# BEE_BOARD_DECAWAVE.net
KiCad netlist of a schematic drawn in Altium Designer
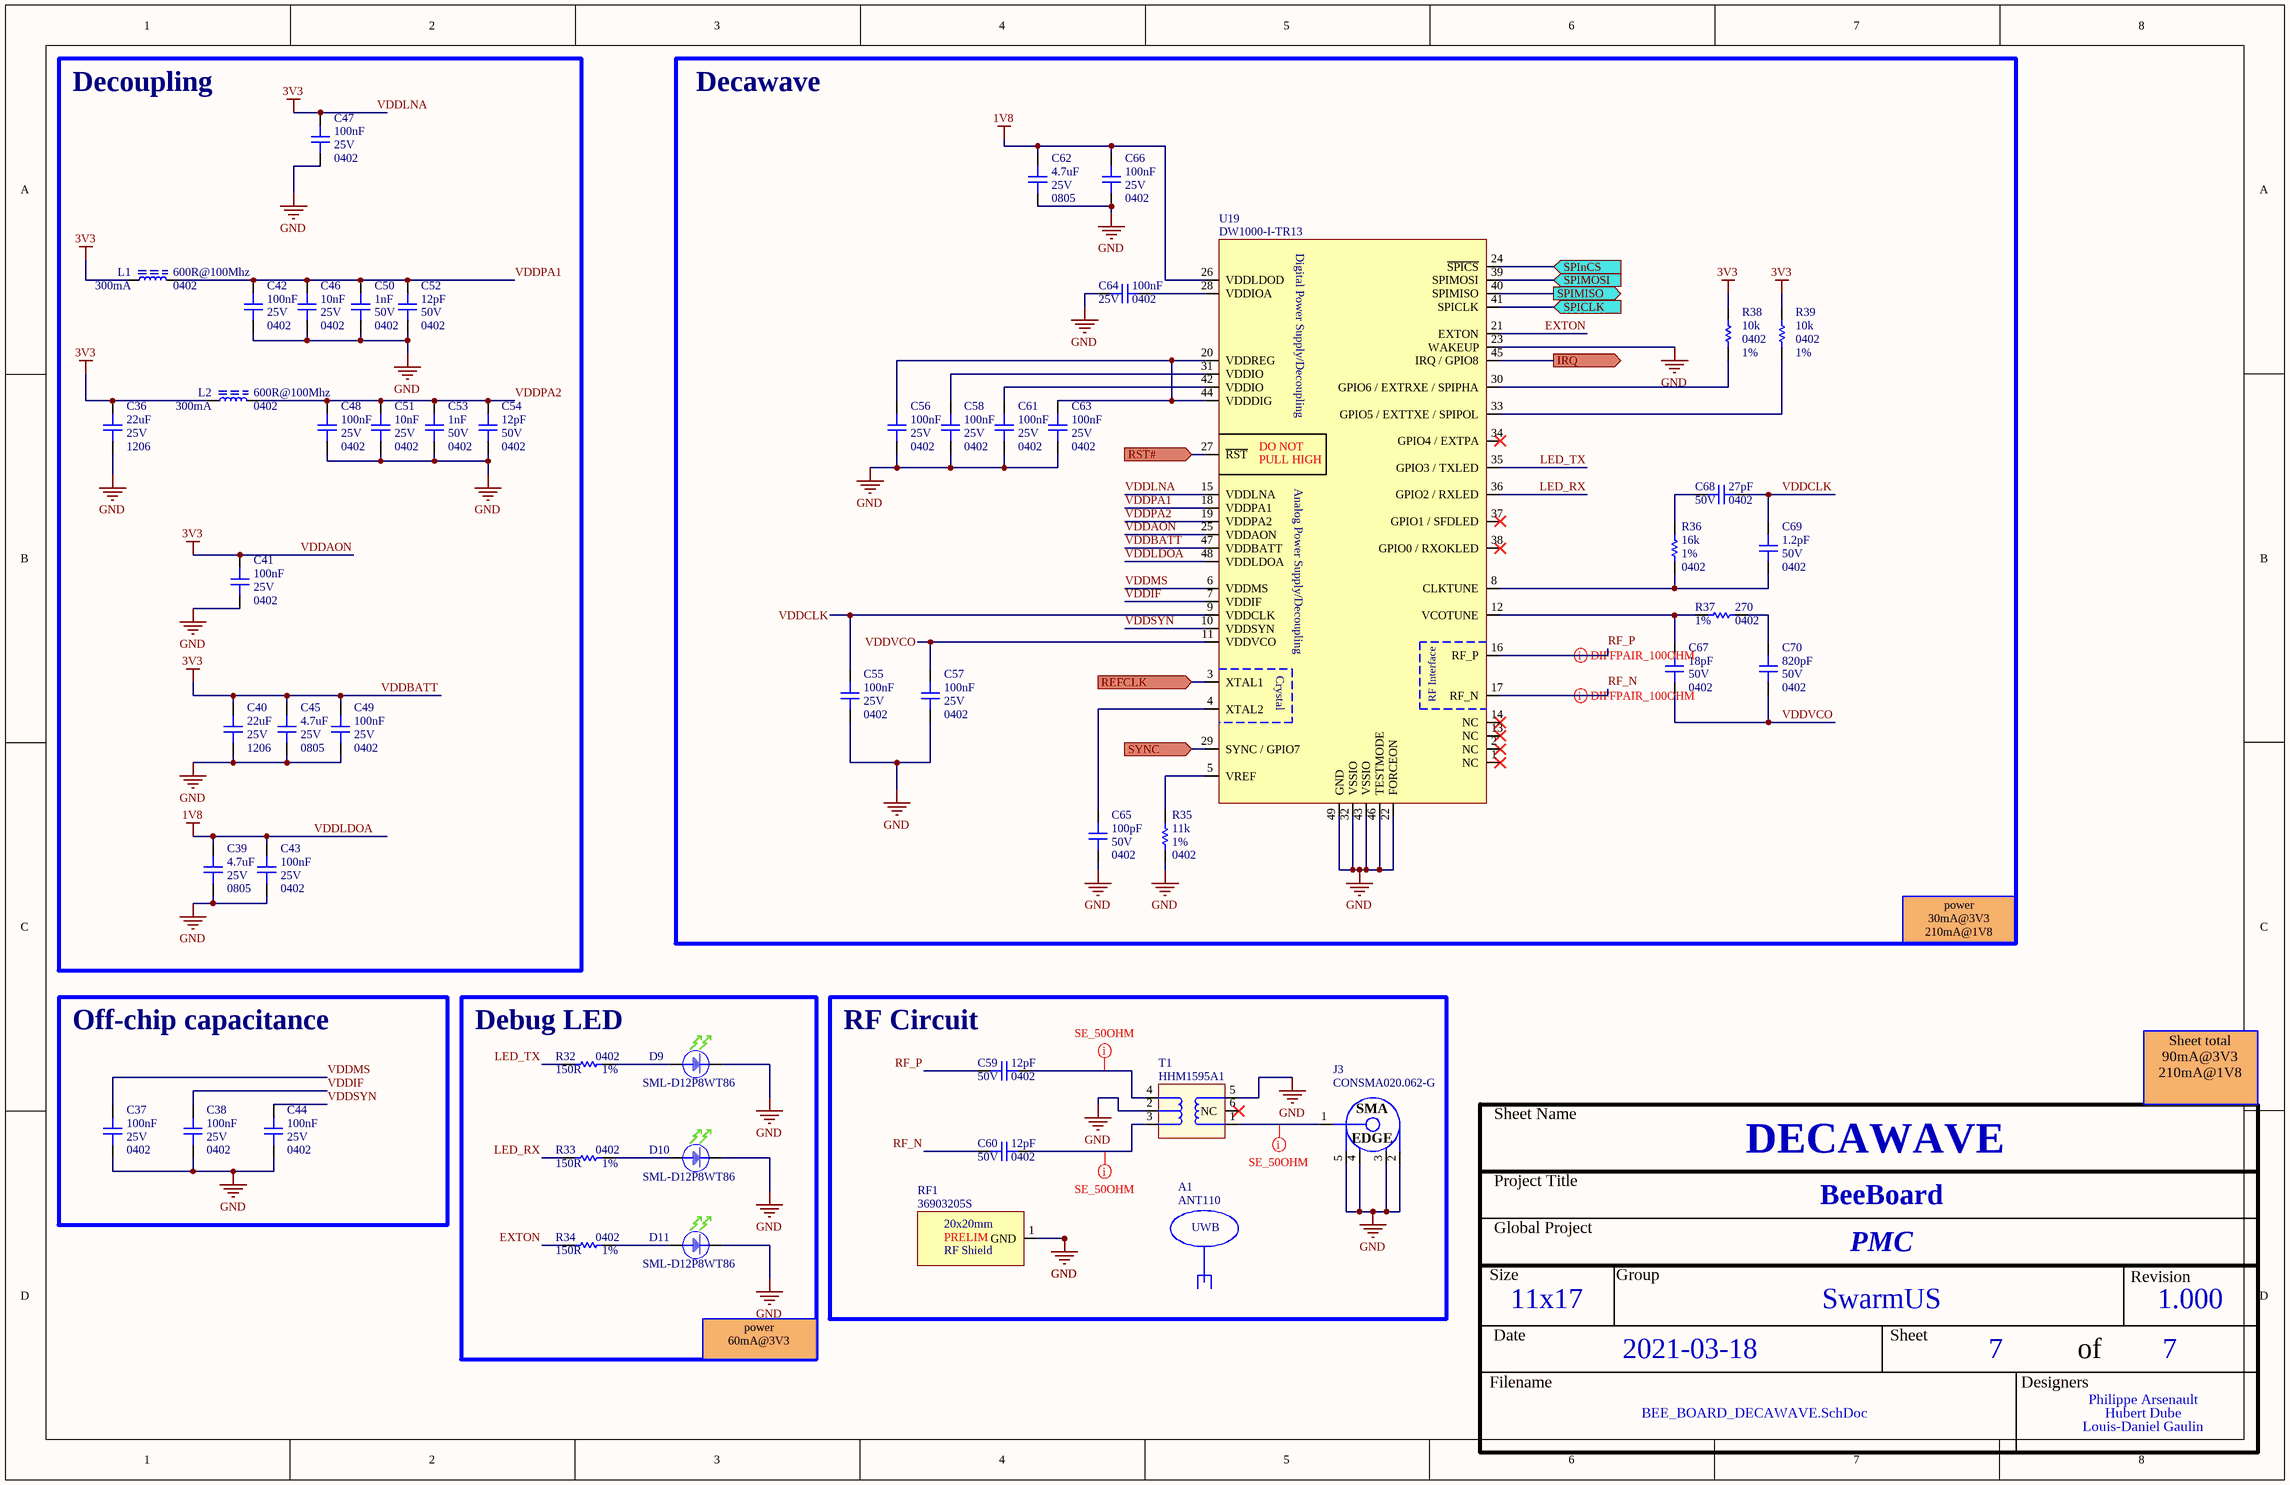
[diagram p0: BEE_BOARD_DECAWAVE.SchDoc]

(export (version "E")
  (design (tool "Eeschema 10.0.6"))
  (components
    (comp (ref "A1")
      (value "ANT110")
      (description "ANT - UWB antenna 3.2 to 7GHz")
      (fields
        (field (name "CREATEDBY/DATE") "Philippe Arsenault/2021-04-11")
        (field (name "VERIFIEDBY") "Louis-Daniel Gaulin / 14-04-2021")
      )
      (libsource (lib "SWARMUS_LIB") (part "ANT_ANT110"))
    )
    (comp (ref "C36")
      (value "22uF")
      (footprint "grams_master_lib_pcb:CAP_CER_1206")
      (description "CAP - CER 22uF 10% 25V X5R - 1206")
      (fields
        (field (name "TOLERANCE") "10%")
        (field (name "PACKAGE") "1206")
        (field (name "VOLTAGE RATING") "25V")
        (field (name "Comment") "CL31A226KAHNNNE")
        (field (name "CREATEDBY/DATE") "Philippe Arsenault/21 Janvier 2020")
        (field (name "VERIFIEDBY") "C.Paulin - 28/01/2020")
      )
      (libsource (lib "GRAMS_MASTER_LIB_SCH") (part "CAP_CER_CL31A226KAHNNNE"))
    )
    (comp (ref "C37")
      (value "100nF")
      (footprint "GRAMS_MASTER_LIB_PCB:CAP_CER_0402")
      (description "CAP - CER 0.1µF 10% 25V X7R - 0402")
      (fields
        (field (name "TOLERANCE") "10%")
        (field (name "PACKAGE") "0402")
        (field (name "VOLTAGE RATING") "25V")
        (field (name "Comment") "CGA2B3X7R1E104K050BB")
        (field (name "CREATEDBY/DATE") "Nicolas Roy 2018-11-07")
        (field (name "VERIFIEDBY") "Nicolas V. (2019-01-22)")
      )
      (libsource (lib "GRAMS_MASTER_LIB_SCH") (part "CAP_CER_CGA2B3X7R1E104K050BB"))
    )
    (comp (ref "C38")
      (value "100nF")
      (footprint "GRAMS_MASTER_LIB_PCB:CAP_CER_0402")
      (description "CAP - CER 0.1µF 10% 25V X7R - 0402")
      (fields
        (field (name "TOLERANCE") "10%")
        (field (name "PACKAGE") "0402")
        (field (name "VOLTAGE RATING") "25V")
        (field (name "Comment") "CGA2B3X7R1E104K050BB")
        (field (name "CREATEDBY/DATE") "Nicolas Roy 2018-11-07")
        (field (name "VERIFIEDBY") "Nicolas V. (2019-01-22)")
      )
      (libsource (lib "GRAMS_MASTER_LIB_SCH") (part "CAP_CER_CGA2B3X7R1E104K050BB"))
    )
    (comp (ref "C39")
      (value "4.7uF")
      (footprint "GRAMS_MASTER_LIB_PCB:CAP_CER_0805")
      (description "CAP - CER 4.7UF 10% 25V X7R - 0805")
      (fields
        (field (name "TOLERANCE") "10%")
        (field (name "PACKAGE") "0805")
        (field (name "VOLTAGE RATING") "25V")
        (field (name "Comment") "C2012X7R1E475K125AE")
        (field (name "CREATEDBY/DATE") "Keven Deslandes - 2018/11/09")
        (field (name "VERIFIEDBY") "Nicolas Roy - 2018/12/11")
      )
      (libsource (lib "GRAMS_MASTER_LIB_SCH") (part "CAP_CER_C2012X7R1E475K125AE"))
    )
    (comp (ref "C40")
      (value "22uF")
      (footprint "grams_master_lib_pcb:CAP_CER_1206")
      (description "CAP - CER 22uF 10% 25V X5R - 1206")
      (fields
        (field (name "TOLERANCE") "10%")
        (field (name "PACKAGE") "1206")
        (field (name "VOLTAGE RATING") "25V")
        (field (name "Comment") "CL31A226KAHNNNE")
        (field (name "CREATEDBY/DATE") "Philippe Arsenault/21 Janvier 2020")
        (field (name "VERIFIEDBY") "C.Paulin - 28/01/2020")
      )
      (libsource (lib "GRAMS_MASTER_LIB_SCH") (part "CAP_CER_CL31A226KAHNNNE"))
    )
    (comp (ref "C41")
      (value "100nF")
      (footprint "GRAMS_MASTER_LIB_PCB:CAP_CER_0402")
      (description "CAP - CER 0.1µF 10% 25V X7R - 0402")
      (fields
        (field (name "TOLERANCE") "10%")
        (field (name "PACKAGE") "0402")
        (field (name "VOLTAGE RATING") "25V")
        (field (name "Comment") "CGA2B3X7R1E104K050BB")
        (field (name "CREATEDBY/DATE") "Nicolas Roy 2018-11-07")
        (field (name "VERIFIEDBY") "Nicolas V. (2019-01-22)")
      )
      (libsource (lib "GRAMS_MASTER_LIB_SCH") (part "CAP_CER_CGA2B3X7R1E104K050BB"))
    )
    (comp (ref "C42")
      (value "100nF")
      (footprint "GRAMS_MASTER_LIB_PCB:CAP_CER_0402")
      (description "CAP - CER 0.1µF 10% 25V X7R - 0402")
      (fields
        (field (name "TOLERANCE") "10%")
        (field (name "PACKAGE") "0402")
        (field (name "VOLTAGE RATING") "25V")
        (field (name "Comment") "CGA2B3X7R1E104K050BB")
        (field (name "CREATEDBY/DATE") "Nicolas Roy 2018-11-07")
        (field (name "VERIFIEDBY") "Nicolas V. (2019-01-22)")
      )
      (libsource (lib "GRAMS_MASTER_LIB_SCH") (part "CAP_CER_CGA2B3X7R1E104K050BB"))
    )
    (comp (ref "C43")
      (value "100nF")
      (footprint "GRAMS_MASTER_LIB_PCB:CAP_CER_0402")
      (description "CAP - CER 0.1µF 10% 25V X7R - 0402")
      (fields
        (field (name "TOLERANCE") "10%")
        (field (name "PACKAGE") "0402")
        (field (name "VOLTAGE RATING") "25V")
        (field (name "Comment") "CGA2B3X7R1E104K050BB")
        (field (name "CREATEDBY/DATE") "Nicolas Roy 2018-11-07")
        (field (name "VERIFIEDBY") "Nicolas V. (2019-01-22)")
      )
      (libsource (lib "GRAMS_MASTER_LIB_SCH") (part "CAP_CER_CGA2B3X7R1E104K050BB"))
    )
    (comp (ref "C44")
      (value "100nF")
      (footprint "GRAMS_MASTER_LIB_PCB:CAP_CER_0402")
      (description "CAP - CER 0.1µF 10% 25V X7R - 0402")
      (fields
        (field (name "TOLERANCE") "10%")
        (field (name "PACKAGE") "0402")
        (field (name "VOLTAGE RATING") "25V")
        (field (name "Comment") "CGA2B3X7R1E104K050BB")
        (field (name "CREATEDBY/DATE") "Nicolas Roy 2018-11-07")
        (field (name "VERIFIEDBY") "Nicolas V. (2019-01-22)")
      )
      (libsource (lib "GRAMS_MASTER_LIB_SCH") (part "CAP_CER_CGA2B3X7R1E104K050BB"))
    )
    (comp (ref "C45")
      (value "4.7uF")
      (footprint "GRAMS_MASTER_LIB_PCB:CAP_CER_0805")
      (description "CAP - CER 4.7UF 10% 25V X7R - 0805")
      (fields
        (field (name "TOLERANCE") "10%")
        (field (name "PACKAGE") "0805")
        (field (name "VOLTAGE RATING") "25V")
        (field (name "Comment") "C2012X7R1E475K125AE")
        (field (name "CREATEDBY/DATE") "Keven Deslandes - 2018/11/09")
        (field (name "VERIFIEDBY") "Nicolas Roy - 2018/12/11")
      )
      (libsource (lib "GRAMS_MASTER_LIB_SCH") (part "CAP_CER_C2012X7R1E475K125AE"))
    )
    (comp (ref "C46")
      (value "10nF")
      (footprint "GRAMS_MASTER_LIB_PCB:CAP_CER_0402")
      (description "CAP - CER 10nF 10% 25V X7R - 0402")
      (fields
        (field (name "TOLERANCE") "10%")
        (field (name "PACKAGE") "0402")
        (field (name "VOLTAGE RATING") "25V")
        (field (name "Comment") "CL05B103KA5NNNC")
        (field (name "CREATEDBY/DATE") "Romain Espagnet 2018-07-16")
        (field (name "VERIFIEDBY") "Jonathan Bouchard 2018-07-30")
      )
      (libsource (lib "GRAMS_MASTER_LIB_SCH") (part "CAP_CER_CL05B103KA5NNNC"))
    )
    (comp (ref "C47")
      (value "100nF")
      (footprint "GRAMS_MASTER_LIB_PCB:CAP_CER_0402")
      (description "CAP - CER 0.1µF 10% 25V X7R - 0402")
      (fields
        (field (name "TOLERANCE") "10%")
        (field (name "PACKAGE") "0402")
        (field (name "VOLTAGE RATING") "25V")
        (field (name "Comment") "CGA2B3X7R1E104K050BB")
        (field (name "CREATEDBY/DATE") "Nicolas Roy 2018-11-07")
        (field (name "VERIFIEDBY") "Nicolas V. (2019-01-22)")
      )
      (libsource (lib "GRAMS_MASTER_LIB_SCH") (part "CAP_CER_CGA2B3X7R1E104K050BB"))
    )
    (comp (ref "C48")
      (value "100nF")
      (footprint "GRAMS_MASTER_LIB_PCB:CAP_CER_0402")
      (description "CAP - CER 0.1µF 10% 25V X7R - 0402")
      (fields
        (field (name "TOLERANCE") "10%")
        (field (name "PACKAGE") "0402")
        (field (name "VOLTAGE RATING") "25V")
        (field (name "Comment") "CGA2B3X7R1E104K050BB")
        (field (name "CREATEDBY/DATE") "Nicolas Roy 2018-11-07")
        (field (name "VERIFIEDBY") "Nicolas V. (2019-01-22)")
      )
      (libsource (lib "GRAMS_MASTER_LIB_SCH") (part "CAP_CER_CGA2B3X7R1E104K050BB"))
    )
    (comp (ref "C49")
      (value "100nF")
      (footprint "GRAMS_MASTER_LIB_PCB:CAP_CER_0402")
      (description "CAP - CER 0.1µF 10% 25V X7R - 0402")
      (fields
        (field (name "TOLERANCE") "10%")
        (field (name "PACKAGE") "0402")
        (field (name "VOLTAGE RATING") "25V")
        (field (name "Comment") "CGA2B3X7R1E104K050BB")
        (field (name "CREATEDBY/DATE") "Nicolas Roy 2018-11-07")
        (field (name "VERIFIEDBY") "Nicolas V. (2019-01-22)")
      )
      (libsource (lib "GRAMS_MASTER_LIB_SCH") (part "CAP_CER_CGA2B3X7R1E104K050BB"))
    )
    (comp (ref "C50")
      (value "1nF")
      (footprint "CAP_CER_0402")
      (description "CAP - CER 1nF 10% 50V X7R - 0402")
      (fields
        (field (name "TOLERANCE") "10%")
        (field (name "PACKAGE") "0402")
        (field (name "VOLTAGE RATING") "50V")
        (field (name "Comment") "CC0402KRX7R9BB102")
        (field (name "CREATEDBY/DATE") "Jonathan Bouchard 2019-04-06")
        (field (name "VERIFIEDBY") "Nicolas V. (2019-04-30)")
      )
      (libsource (lib "GRAMS_MASTER_LIB_SCH") (part "CAP_CER_CC0402KRX7R9BB102"))
    )
    (comp (ref "C51")
      (value "10nF")
      (footprint "GRAMS_MASTER_LIB_PCB:CAP_CER_0402")
      (description "CAP - CER 10nF 10% 25V X7R - 0402")
      (fields
        (field (name "TOLERANCE") "10%")
        (field (name "PACKAGE") "0402")
        (field (name "VOLTAGE RATING") "25V")
        (field (name "Comment") "CL05B103KA5NNNC")
        (field (name "CREATEDBY/DATE") "Romain Espagnet 2018-07-16")
        (field (name "VERIFIEDBY") "Jonathan Bouchard 2018-07-30")
      )
      (libsource (lib "GRAMS_MASTER_LIB_SCH") (part "CAP_CER_CL05B103KA5NNNC"))
    )
    (comp (ref "C52")
      (value "12pF")
      (footprint "SWARMUS_LIB:CAP_CER_0402")
      (description "CAP - CER 12pF 50V ±5% C0G, NP0 - 0402")
      (fields
        (field (name "TOLERANCE") "±5%")
        (field (name "PACKAGE") "0402")
        (field (name "VOLTAGE RATING") "50V")
        (field (name "Comment") "CC0402JRNPO9BN120")
        (field (name "CREATEDBY/DATE") "Philippe Arsenault/ 2020-07-24")
        (field (name "VERIFIEDBY") "Louis-Daniel Gaulin / 2020-07-29")
      )
      (libsource (lib "SWARMUS_LIB") (part "CAP_CER_CC0402JRNPO9BN120"))
    )
    (comp (ref "C53")
      (value "1nF")
      (footprint "CAP_CER_0402")
      (description "CAP - CER 1nF 10% 50V X7R - 0402")
      (fields
        (field (name "TOLERANCE") "10%")
        (field (name "PACKAGE") "0402")
        (field (name "VOLTAGE RATING") "50V")
        (field (name "Comment") "CC0402KRX7R9BB102")
        (field (name "CREATEDBY/DATE") "Jonathan Bouchard 2019-04-06")
        (field (name "VERIFIEDBY") "Nicolas V. (2019-04-30)")
      )
      (libsource (lib "GRAMS_MASTER_LIB_SCH") (part "CAP_CER_CC0402KRX7R9BB102"))
    )
    (comp (ref "C54")
      (value "12pF")
      (footprint "SWARMUS_LIB:CAP_CER_0402")
      (description "CAP - CER 12pF 50V ±5% C0G, NP0 - 0402")
      (fields
        (field (name "TOLERANCE") "±5%")
        (field (name "PACKAGE") "0402")
        (field (name "VOLTAGE RATING") "50V")
        (field (name "Comment") "CC0402JRNPO9BN120")
        (field (name "CREATEDBY/DATE") "Philippe Arsenault/ 2020-07-24")
        (field (name "VERIFIEDBY") "Louis-Daniel Gaulin / 2020-07-29")
      )
      (libsource (lib "SWARMUS_LIB") (part "CAP_CER_CC0402JRNPO9BN120"))
    )
    (comp (ref "C55")
      (value "100nF")
      (footprint "GRAMS_MASTER_LIB_PCB:CAP_CER_0402")
      (description "CAP - CER 0.1µF 10% 25V X7R - 0402")
      (fields
        (field (name "TOLERANCE") "10%")
        (field (name "PACKAGE") "0402")
        (field (name "VOLTAGE RATING") "25V")
        (field (name "Comment") "CGA2B3X7R1E104K050BB")
        (field (name "CREATEDBY/DATE") "Nicolas Roy 2018-11-07")
        (field (name "VERIFIEDBY") "Nicolas V. (2019-01-22)")
      )
      (libsource (lib "GRAMS_MASTER_LIB_SCH") (part "CAP_CER_CGA2B3X7R1E104K050BB"))
    )
    (comp (ref "C56")
      (value "100nF")
      (footprint "GRAMS_MASTER_LIB_PCB:CAP_CER_0402")
      (description "CAP - CER 0.1µF 10% 25V X7R - 0402")
      (fields
        (field (name "TOLERANCE") "10%")
        (field (name "PACKAGE") "0402")
        (field (name "VOLTAGE RATING") "25V")
        (field (name "Comment") "CGA2B3X7R1E104K050BB")
        (field (name "CREATEDBY/DATE") "Nicolas Roy 2018-11-07")
        (field (name "VERIFIEDBY") "Nicolas V. (2019-01-22)")
      )
      (libsource (lib "GRAMS_MASTER_LIB_SCH") (part "CAP_CER_CGA2B3X7R1E104K050BB"))
    )
    (comp (ref "C57")
      (value "100nF")
      (footprint "GRAMS_MASTER_LIB_PCB:CAP_CER_0402")
      (description "CAP - CER 0.1µF 10% 25V X7R - 0402")
      (fields
        (field (name "TOLERANCE") "10%")
        (field (name "PACKAGE") "0402")
        (field (name "VOLTAGE RATING") "25V")
        (field (name "Comment") "CGA2B3X7R1E104K050BB")
        (field (name "CREATEDBY/DATE") "Nicolas Roy 2018-11-07")
        (field (name "VERIFIEDBY") "Nicolas V. (2019-01-22)")
      )
      (libsource (lib "GRAMS_MASTER_LIB_SCH") (part "CAP_CER_CGA2B3X7R1E104K050BB"))
    )
    (comp (ref "C58")
      (value "100nF")
      (footprint "GRAMS_MASTER_LIB_PCB:CAP_CER_0402")
      (description "CAP - CER 0.1µF 10% 25V X7R - 0402")
      (fields
        (field (name "TOLERANCE") "10%")
        (field (name "PACKAGE") "0402")
        (field (name "VOLTAGE RATING") "25V")
        (field (name "Comment") "CGA2B3X7R1E104K050BB")
        (field (name "CREATEDBY/DATE") "Nicolas Roy 2018-11-07")
        (field (name "VERIFIEDBY") "Nicolas V. (2019-01-22)")
      )
      (libsource (lib "GRAMS_MASTER_LIB_SCH") (part "CAP_CER_CGA2B3X7R1E104K050BB"))
    )
    (comp (ref "C59")
      (value "12pF")
      (footprint "SWARMUS_LIB:CAP_CER_0402")
      (description "CAP - CER 12pF 50V ±5% C0G, NP0 - 0402")
      (fields
        (field (name "TOLERANCE") "±5%")
        (field (name "PACKAGE") "0402")
        (field (name "VOLTAGE RATING") "50V")
        (field (name "Comment") "CC0402JRNPO9BN120")
        (field (name "CREATEDBY/DATE") "Philippe Arsenault/ 2020-07-24")
        (field (name "VERIFIEDBY") "Louis-Daniel Gaulin / 2020-07-29")
      )
      (libsource (lib "SWARMUS_LIB") (part "CAP_CER_CC0402JRNPO9BN120"))
    )
    (comp (ref "C60")
      (value "12pF")
      (footprint "SWARMUS_LIB:CAP_CER_0402")
      (description "CAP - CER 12pF 50V ±5% C0G, NP0 - 0402")
      (fields
        (field (name "TOLERANCE") "±5%")
        (field (name "PACKAGE") "0402")
        (field (name "VOLTAGE RATING") "50V")
        (field (name "Comment") "CC0402JRNPO9BN120")
        (field (name "CREATEDBY/DATE") "Philippe Arsenault/ 2020-07-24")
        (field (name "VERIFIEDBY") "Louis-Daniel Gaulin / 2020-07-29")
      )
      (libsource (lib "SWARMUS_LIB") (part "CAP_CER_CC0402JRNPO9BN120"))
    )
    (comp (ref "C61")
      (value "100nF")
      (footprint "GRAMS_MASTER_LIB_PCB:CAP_CER_0402")
      (description "CAP - CER 0.1µF 10% 25V X7R - 0402")
      (fields
        (field (name "TOLERANCE") "10%")
        (field (name "PACKAGE") "0402")
        (field (name "VOLTAGE RATING") "25V")
        (field (name "Comment") "CGA2B3X7R1E104K050BB")
        (field (name "CREATEDBY/DATE") "Nicolas Roy 2018-11-07")
        (field (name "VERIFIEDBY") "Nicolas V. (2019-01-22)")
      )
      (libsource (lib "GRAMS_MASTER_LIB_SCH") (part "CAP_CER_CGA2B3X7R1E104K050BB"))
    )
    (comp (ref "C62")
      (value "4.7uF")
      (footprint "GRAMS_MASTER_LIB_PCB:CAP_CER_0805")
      (description "CAP - CER 4.7UF 10% 25V X7R - 0805")
      (fields
        (field (name "TOLERANCE") "10%")
        (field (name "PACKAGE") "0805")
        (field (name "VOLTAGE RATING") "25V")
        (field (name "Comment") "C2012X7R1E475K125AE")
        (field (name "CREATEDBY/DATE") "Keven Deslandes - 2018/11/09")
        (field (name "VERIFIEDBY") "Nicolas Roy - 2018/12/11")
      )
      (libsource (lib "GRAMS_MASTER_LIB_SCH") (part "CAP_CER_C2012X7R1E475K125AE"))
    )
    (comp (ref "C63")
      (value "100nF")
      (footprint "GRAMS_MASTER_LIB_PCB:CAP_CER_0402")
      (description "CAP - CER 0.1µF 10% 25V X7R - 0402")
      (fields
        (field (name "TOLERANCE") "10%")
        (field (name "PACKAGE") "0402")
        (field (name "VOLTAGE RATING") "25V")
        (field (name "Comment") "CGA2B3X7R1E104K050BB")
        (field (name "CREATEDBY/DATE") "Nicolas Roy 2018-11-07")
        (field (name "VERIFIEDBY") "Nicolas V. (2019-01-22)")
      )
      (libsource (lib "GRAMS_MASTER_LIB_SCH") (part "CAP_CER_CGA2B3X7R1E104K050BB"))
    )
    (comp (ref "C64")
      (value "100nF")
      (footprint "GRAMS_MASTER_LIB_PCB:CAP_CER_0402")
      (description "CAP - CER 0.1µF 10% 25V X7R - 0402")
      (fields
        (field (name "TOLERANCE") "10%")
        (field (name "PACKAGE") "0402")
        (field (name "VOLTAGE RATING") "25V")
        (field (name "Comment") "CGA2B3X7R1E104K050BB")
        (field (name "CREATEDBY/DATE") "Nicolas Roy 2018-11-07")
        (field (name "VERIFIEDBY") "Nicolas V. (2019-01-22)")
      )
      (libsource (lib "GRAMS_MASTER_LIB_SCH") (part "CAP_CER_CGA2B3X7R1E104K050BB"))
    )
    (comp (ref "C65")
      (value "100pF")
      (footprint "SWARMUS_LIB:CAP_CER_0402")
      (description "CAP - CER 100pF 50V ±5% C0G,CP0 - 0402")
      (fields
        (field (name "TOLERANCE") "±5%")
        (field (name "PACKAGE") "0402")
        (field (name "VOLTAGE RATING") "50V")
        (field (name "Comment") "CC0402JRNPO9BN101")
        (field (name "CREATEDBY/DATE") "Philippe Arsenault/ 2020-07-24")
        (field (name "VERIFIEDBY") "Louis-Daniel Gaulin / 2020-07-29")
      )
      (libsource (lib "SWARMUS_LIB") (part "CAP_CER_CC0402JRNPO9BN101"))
    )
    (comp (ref "C66")
      (value "100nF")
      (footprint "GRAMS_MASTER_LIB_PCB:CAP_CER_0402")
      (description "CAP - CER 0.1µF 10% 25V X7R - 0402")
      (fields
        (field (name "TOLERANCE") "10%")
        (field (name "PACKAGE") "0402")
        (field (name "VOLTAGE RATING") "25V")
        (field (name "Comment") "CGA2B3X7R1E104K050BB")
        (field (name "CREATEDBY/DATE") "Nicolas Roy 2018-11-07")
        (field (name "VERIFIEDBY") "Nicolas V. (2019-01-22)")
      )
      (libsource (lib "GRAMS_MASTER_LIB_SCH") (part "CAP_CER_CGA2B3X7R1E104K050BB"))
    )
    (comp (ref "C67")
      (value "18pF")
      (footprint "CAP_CER_0402")
      (description "CAP - CER 18pF 50V C0G, NPO - 0402")
      (fields
        (field (name "TOLERANCE") "2%")
        (field (name "PACKAGE") "0402")
        (field (name "VOLTAGE RATING") "50V")
        (field (name "Comment") "GRM1555C1H180GA01D")
        (field (name "CREATEDBY/DATE") "Tommy Rossignol / 2018-11-20")
        (field (name "VERIFIEDBY") "Caroline Paulin - 13 fév 2019")
      )
      (libsource (lib "GRAMS_MASTER_LIB_SCH") (part "CAP_CER_GRM1555C1H180GA01D"))
    )
    (comp (ref "C68")
      (value "27pF")
      (footprint "SWARMUS_LIB:CAP_CER_0402")
      (description "CAP - CER 27pF 50V ±5% C0G, NP0 - 0402")
      (fields
        (field (name "TOLERANCE") "±5%")
        (field (name "PACKAGE") "0402")
        (field (name "VOLTAGE RATING") "50V")
        (field (name "Comment") "CC0402JRNPO9BN270")
        (field (name "CREATEDBY/DATE") "Philippe Arsenault/ 2020-07-24")
        (field (name "VERIFIEDBY") "Louis-Daniel Gaulin / 2020-07-29")
      )
      (libsource (lib "SWARMUS_LIB") (part "CAP_CER_CC0402JRNPO9BN270"))
    )
    (comp (ref "C69")
      (value "1.2pF")
      (footprint "SWARMUS_LIB:CAP_CER_0402")
      (description "CAP - CER 1.2pF 50V ±0.25pF C0G, NP0 - 0402")
      (fields
        (field (name "TOLERANCE") "±0.25pF")
        (field (name "PACKAGE") "0402")
        (field (name "VOLTAGE RATING") "50V")
        (field (name "Comment") "C0402C129C5GACTU")
        (field (name "CREATEDBY/DATE") "Philippe Arsenault/ 2020-07-24")
        (field (name "VERIFIEDBY") "Louis-Daniel Gaulin / 2020-07-29")
      )
      (libsource (lib "SWARMUS_LIB") (part "CAP_CER_C0402C129C5GACTU"))
    )
    (comp (ref "C70")
      (value "820pF")
      (footprint "SWARMUS_LIB:CAP_CER_0402")
      (description "CAP - CER 820pF 50V ±10% X7R - 0402")
      (fields
        (field (name "TOLERANCE") "±10%")
        (field (name "PACKAGE") "0402")
        (field (name "VOLTAGE RATING") "50V")
        (field (name "Comment") "CC0402KRX7R9BB821")
        (field (name "CREATEDBY/DATE") "Philippe Arsenault/ 2020-07-24")
        (field (name "VERIFIEDBY") "Louis-Daniel Gaulin / 2020-07-29")
      )
      (libsource (lib "SWARMUS_LIB") (part "CAP_CER_CC0402KRX7R9BB821"))
    )
    (comp (ref "D9")
      (value "SML-D12P8WT86")
      (footprint "GRAMS_MASTER_LIB_PCB:LED_SML-D12P8WT86")
      (description "LED - GREEN DIFFUSED 0603 SMD - 0603")
      (fields
        (field (name "CREATEDBY/DATE") "Keven Deslandes - 2018/11/21")
        (field (name "VERIFIEDBY") "Caroline Paulin - 13 février 2019")
      )
      (libsource (lib "GRAMS_MASTER_LIB_SCH") (part "LED_SML-D12P8WT86"))
    )
    (comp (ref "D10")
      (value "SML-D12P8WT86")
      (footprint "GRAMS_MASTER_LIB_PCB:LED_SML-D12P8WT86")
      (description "LED - GREEN DIFFUSED 0603 SMD - 0603")
      (fields
        (field (name "CREATEDBY/DATE") "Keven Deslandes - 2018/11/21")
        (field (name "VERIFIEDBY") "Caroline Paulin - 13 février 2019")
      )
      (libsource (lib "GRAMS_MASTER_LIB_SCH") (part "LED_SML-D12P8WT86"))
    )
    (comp (ref "D11")
      (value "SML-D12P8WT86")
      (footprint "GRAMS_MASTER_LIB_PCB:LED_SML-D12P8WT86")
      (description "LED - GREEN DIFFUSED 0603 SMD - 0603")
      (fields
        (field (name "CREATEDBY/DATE") "Keven Deslandes - 2018/11/21")
        (field (name "VERIFIEDBY") "Caroline Paulin - 13 février 2019")
      )
      (libsource (lib "GRAMS_MASTER_LIB_SCH") (part "LED_SML-D12P8WT86"))
    )
    (comp (ref "J3")
      (value "CONSMA020.062-G")
      (footprint "CON_SMA_CONSMA020.062-G")
      (description "CON_SMA FML EDGE MNT 0.062\" PCB - 5-SMD")
      (fields (field (name "CREATEDBY/DATE") "Philippe Arsenault/2021-03-26"))
      (libsource (lib "SWARMUS_LIB") (part "CON_SMA_CONSMA020.062-G"))
    )
    (comp (ref "L1")
      (value "600R@100Mhz")
      (footprint "FER_0402")
      (description "FER - FERRITE BEAD 600 OHM@100MHz - 0402")
      (fields
        (field (name "CURRENT RATING") "300mA")
        (field (name "PACKAGE") "0402")
        (field (name "Comment") "BLM15AG601SN1D")
        (field (name "CREATEDBY/DATE") "Philippe Arsenault/2020-07-24")
      )
      (libsource (lib "a_Valider_PA") (part "FER_BLM15AG601SN1D"))
    )
    (comp (ref "L2")
      (value "600R@100Mhz")
      (footprint "FER_0402")
      (description "FER - FERRITE BEAD 600 OHM@100MHz - 0402")
      (fields
        (field (name "CURRENT RATING") "300mA")
        (field (name "PACKAGE") "0402")
        (field (name "Comment") "BLM15AG601SN1D")
        (field (name "CREATEDBY/DATE") "Philippe Arsenault/2020-07-24")
      )
      (libsource (lib "a_Valider_PA") (part "FER_BLM15AG601SN1D"))
    )
    (comp (ref "R32")
      (value "150R")
      (footprint "RES_0402")
      (description "RES - 150R 1% 1/16W - 0402")
      (fields
        (field (name "TOLERANCE") "1%")
        (field (name "PACKAGE") "0402")
        (field (name "Comment") "RC0402FR-07150RL")
        (field (name "CREATEDBY/DATE") "Jonathan Bouchard 2019-03-25")
        (field (name "VERIFIEDBY") "Nicolas V. (2019-05-02)")
      )
      (libsource (lib "GRAMS_MASTER_LIB_SCH") (part "RES_RC0402FR-07150RL"))
    )
    (comp (ref "R33")
      (value "150R")
      (footprint "RES_0402")
      (description "RES - 150R 1% 1/16W - 0402")
      (fields
        (field (name "TOLERANCE") "1%")
        (field (name "PACKAGE") "0402")
        (field (name "Comment") "RC0402FR-07150RL")
        (field (name "CREATEDBY/DATE") "Jonathan Bouchard 2019-03-25")
        (field (name "VERIFIEDBY") "Nicolas V. (2019-05-02)")
      )
      (libsource (lib "GRAMS_MASTER_LIB_SCH") (part "RES_RC0402FR-07150RL"))
    )
    (comp (ref "R34")
      (value "150R")
      (footprint "RES_0402")
      (description "RES - 150R 1% 1/16W - 0402")
      (fields
        (field (name "TOLERANCE") "1%")
        (field (name "PACKAGE") "0402")
        (field (name "Comment") "RC0402FR-07150RL")
        (field (name "CREATEDBY/DATE") "Jonathan Bouchard 2019-03-25")
        (field (name "VERIFIEDBY") "Nicolas V. (2019-05-02)")
      )
      (libsource (lib "GRAMS_MASTER_LIB_SCH") (part "RES_RC0402FR-07150RL"))
    )
    (comp (ref "R35")
      (value "11k")
      (footprint "GRAMS_MASTER_LIB_PCB:RES_0402")
      (description "RES - 11K 1% 1/16W - 0402")
      (fields
        (field (name "TOLERANCE") "1%")
        (field (name "PACKAGE") "0402")
        (field (name "Comment") "RC0402FR-0711KL")
        (field (name "CREATEDBY/DATE") "Keven Deslandes 2018-10-15")
        (field (name "VERIFIEDBY") "Carolilne Paulin - 18/12/2018")
      )
      (libsource (lib "GRAMS_MASTER_LIB_SCH") (part "RES_RC0402FR-0711KL"))
    )
    (comp (ref "R36")
      (value "16k")
      (footprint "GRAMS_MASTER_LIB_PCB:RES_0402")
      (description "RES - 16k OHM 1% 1/16W - 0402")
      (fields
        (field (name "TOLERANCE") "1%")
        (field (name "PACKAGE") "0402")
        (field (name "Comment") "RC0402FR-0716KL")
        (field (name "CREATEDBY/DATE") "Nicolas Roy/18 oct. 2018")
        (field (name "VERIFIEDBY") "Caroline Paulin - 18/12/2018")
      )
      (libsource (lib "GRAMS_MASTER_LIB_SCH") (part "RES_RC0402FR-0716KL"))
    )
    (comp (ref "R37")
      (value "270")
      (footprint "FER_0402")
      (description "RES - 270R 1% 1/16W - 0402")
      (fields
        (field (name "TOLERANCE") "1%")
        (field (name "PACKAGE") "0402")
        (field (name "Comment") "RC0402FR-07270RL")
        (field (name "CREATEDBY/DATE") "Philippe Arsenault 2020-07-24")
        (field (name "VERIFIEDBY") "Louis-Daniel Gaulin / 03-10-2020")
      )
      (libsource (lib "SWARMUS_LIB") (part "RES_RC0402FR-07270RL"))
    )
    (comp (ref "R38")
      (value "10k")
      (footprint "GRAMS_MASTER_LIB_PCB:RES_0402")
      (description "RES - 10K OHMS 1% 1/16W - 0402")
      (fields
        (field (name "TOLERANCE") "1%")
        (field (name "PACKAGE") "0402")
        (field (name "Comment") "RC0402FR-0710KL")
        (field (name "CREATEDBY/DATE") "Nicolas V. (2018-11-20)")
        (field (name "VERIFIEDBY") "Nicolas V. (2018-11-20)")
      )
      (libsource (lib "GRAMS_MASTER_LIB_SCH") (part "RES_RC0402FR-0710KL"))
    )
    (comp (ref "R39")
      (value "10k")
      (footprint "GRAMS_MASTER_LIB_PCB:RES_0402")
      (description "RES - 10K OHMS 1% 1/16W - 0402")
      (fields
        (field (name "TOLERANCE") "1%")
        (field (name "PACKAGE") "0402")
        (field (name "Comment") "RC0402FR-0710KL")
        (field (name "CREATEDBY/DATE") "Nicolas V. (2018-11-20)")
        (field (name "VERIFIEDBY") "Nicolas V. (2018-11-20)")
      )
      (libsource (lib "GRAMS_MASTER_LIB_SCH") (part "RES_RC0402FR-0710KL"))
    )
    (comp (ref "RF1")
      (value "36903205S")
      (footprint "RF_SH_36903205S")
      (description "RF_SH -  RF COVER 0.787\" SNAP FIT")
      (fields (field (name "CREATEDBY/DATE") "Philippe Arsenault/2021-04-17"))
      (libsource (lib "a_Valider_PA") (part "RF_SH_36903205S"))
    )
    (comp (ref "T1")
      (value "HHM1595A1")
      (footprint "XFR_HHM1595A1")
      (description "XFR - Imp Unbalaced/Balanced 50/100 3-8GHz  -SMD")
      (fields
        (field (name "CREATEDBY/DATE") "Philippe Arsenault/2020-21-07")
        (field (name "VERIFIEDBY") "Louis-Daniel Gaulin / 03-10-2020")
      )
      (libsource (lib "SWARMUS_LIB") (part "XFR_HHM1595A1"))
    )
    (comp (ref "U19")
      (value "DW1000-I-TR13")
      (footprint "SWARMUS_LIB:COM_XCV_DW1000-I-TR13")
      (description "COM - IC RF TxRx 802.15.4 IR-UWB DECAWAVE - 48-VFQFN EP")
      (fields (field (name "CREATEDBY/DATE") "Philippe Arsenault/13-07-2020"))
      (libsource (lib "SWARMUS_LIB") (part "COM_XCV_DW1000-I-TR13"))
    )
  )
  (nets
    (net (code "1") (name "/EXTON") (class "Default")
      (node (ref "R34") (pin "2") (pinfunction "2_2") (pintype "passive"))
      (node (ref "U19") (pin "21") (pinfunction "EXTON_21") (pintype "passive"))
    )
    (net (code "2") (name "/IRQ") (class "Default")
      (node (ref "U19") (pin "45") (pinfunction "IRQ_/_GPIO8_45") (pintype "passive"))
    )
    (net (code "3") (name "/LED_RX") (class "Default")
      (node (ref "R33") (pin "2") (pinfunction "2_2") (pintype "passive"))
      (node (ref "U19") (pin "36") (pinfunction "GPIO2_/_RXLED_36") (pintype "passive"))
    )
    (net (code "4") (name "/LED_TX") (class "Default")
      (node (ref "R32") (pin "2") (pinfunction "2_2") (pintype "passive"))
      (node (ref "U19") (pin "35") (pinfunction "GPIO3_/_TXLED_35") (pintype "passive"))
    )
    (net (code "5") (name "/REFCLK") (class "Default")
      (node (ref "U19") (pin "3") (pinfunction "XTAL1_3") (pintype "passive"))
    )
    (net (code "6") (name "/RF_N") (class "Default")
      (node (ref "C60") (pin "2") (pinfunction "2_2") (pintype "passive"))
      (node (ref "U19") (pin "17") (pinfunction "RF_N_17") (pintype "passive"))
    )
    (net (code "7") (name "/RF_P") (class "Default")
      (node (ref "C59") (pin "2") (pinfunction "2_2") (pintype "passive"))
      (node (ref "U19") (pin "16") (pinfunction "RF_P_16") (pintype "passive"))
    )
    (net (code "8") (name "/RST#") (class "Default")
      (node (ref "U19") (pin "27") (pinfunction "RST_27") (pintype "passive"))
    )
    (net (code "9") (name "/SPICLK") (class "Default")
      (node (ref "U19") (pin "41") (pinfunction "SPICLK_41") (pintype "passive"))
    )
    (net (code "10") (name "/SPIMISO") (class "Default")
      (node (ref "U19") (pin "40") (pinfunction "SPIMISO_40") (pintype "passive"))
    )
    (net (code "11") (name "/SPIMOSI") (class "Default")
      (node (ref "U19") (pin "39") (pinfunction "SPIMOSI_39") (pintype "passive"))
    )
    (net (code "12") (name "/SPInCS") (class "Default")
      (node (ref "U19") (pin "24") (pinfunction "SPICS_24") (pintype "passive"))
    )
    (net (code "13") (name "/SYNC") (class "Default")
      (node (ref "U19") (pin "29") (pinfunction "SYNC_/_GPIO7_29") (pintype "passive"))
    )
    (net (code "14") (name "/VDDCLK") (class "Default")
      (node (ref "C55") (pin "2") (pinfunction "2_2") (pintype "passive"))
      (node (ref "C68") (pin "1") (pinfunction "1_1") (pintype "passive"))
      (node (ref "C69") (pin "2") (pinfunction "2_2") (pintype "passive"))
      (node (ref "U19") (pin "9") (pinfunction "VDDCLK_9") (pintype "passive"))
    )
    (net (code "15") (name "/VDDIF") (class "Default")
      (node (ref "C38") (pin "2") (pinfunction "2_2") (pintype "passive"))
      (node (ref "U19") (pin "7") (pinfunction "VDDIF_7") (pintype "passive"))
    )
    (net (code "16") (name "/VDDMS") (class "Default")
      (node (ref "C37") (pin "2") (pinfunction "2_2") (pintype "passive"))
      (node (ref "U19") (pin "6") (pinfunction "VDDMS_6") (pintype "passive"))
    )
    (net (code "17") (name "/VDDPA1") (class "Default")
      (node (ref "C42") (pin "2") (pinfunction "2_2") (pintype "passive"))
      (node (ref "C46") (pin "2") (pinfunction "2_2") (pintype "passive"))
      (node (ref "C50") (pin "2") (pinfunction "2_2") (pintype "passive"))
      (node (ref "C52") (pin "2") (pinfunction "2_2") (pintype "passive"))
      (node (ref "L1") (pin "2") (pinfunction "2_2") (pintype "passive"))
      (node (ref "U19") (pin "18") (pinfunction "VDDPA1_18") (pintype "passive"))
    )
    (net (code "18") (name "/VDDPA2") (class "Default")
      (node (ref "C48") (pin "2") (pinfunction "2_2") (pintype "passive"))
      (node (ref "C51") (pin "2") (pinfunction "2_2") (pintype "passive"))
      (node (ref "C53") (pin "2") (pinfunction "2_2") (pintype "passive"))
      (node (ref "C54") (pin "2") (pinfunction "2_2") (pintype "passive"))
      (node (ref "L2") (pin "2") (pinfunction "2_2") (pintype "passive"))
      (node (ref "U19") (pin "19") (pinfunction "VDDPA2_19") (pintype "passive"))
    )
    (net (code "19") (name "/VDDSYN") (class "Default")
      (node (ref "C44") (pin "2") (pinfunction "2_2") (pintype "passive"))
      (node (ref "U19") (pin "10") (pinfunction "VDDSYN_10") (pintype "passive"))
    )
    (net (code "20") (name "/VDDVCO") (class "Default")
      (node (ref "C57") (pin "2") (pinfunction "2_2") (pintype "passive"))
      (node (ref "C67") (pin "1") (pinfunction "1_1") (pintype "passive"))
      (node (ref "C70") (pin "1") (pinfunction "1_1") (pintype "passive"))
      (node (ref "U19") (pin "11") (pinfunction "VDDVCO_11") (pintype "passive"))
    )
    (net (code "21") (name "1V8") (class "Default")
      (node (ref "C39") (pin "2") (pinfunction "2_2") (pintype "passive"))
      (node (ref "C43") (pin "2") (pinfunction "2_2") (pintype "passive"))
      (node (ref "C62") (pin "2") (pinfunction "2_2") (pintype "passive"))
      (node (ref "C66") (pin "2") (pinfunction "2_2") (pintype "passive"))
      (node (ref "U19") (pin "26") (pinfunction "VDDLDOD_26") (pintype "passive"))
      (node (ref "U19") (pin "48") (pinfunction "VDDLDOA_48") (pintype "passive"))
    )
    (net (code "22") (name "3V3") (class "Default")
      (node (ref "C36") (pin "2") (pinfunction "2_2") (pintype "passive"))
      (node (ref "C40") (pin "2") (pinfunction "2_2") (pintype "passive"))
      (node (ref "C41") (pin "2") (pinfunction "2_2") (pintype "passive"))
      (node (ref "C45") (pin "2") (pinfunction "2_2") (pintype "passive"))
      (node (ref "C47") (pin "2") (pinfunction "2_2") (pintype "passive"))
      (node (ref "C49") (pin "2") (pinfunction "2_2") (pintype "passive"))
      (node (ref "L1") (pin "1") (pinfunction "1_1") (pintype "passive"))
      (node (ref "L2") (pin "1") (pinfunction "1_1") (pintype "passive"))
      (node (ref "R38") (pin "1") (pinfunction "1_1") (pintype "passive"))
      (node (ref "R39") (pin "1") (pinfunction "1_1") (pintype "passive"))
      (node (ref "U19") (pin "15") (pinfunction "VDDLNA_15") (pintype "passive"))
      (node (ref "U19") (pin "25") (pinfunction "VDDAON_25") (pintype "passive"))
      (node (ref "U19") (pin "47") (pinfunction "VDDBATT_47") (pintype "passive"))
    )
    (net (code "23") (name "GND") (class "Default")
      (node (ref "C36") (pin "1") (pinfunction "1_1") (pintype "passive"))
      (node (ref "C37") (pin "1") (pinfunction "1_1") (pintype "passive"))
      (node (ref "C38") (pin "1") (pinfunction "1_1") (pintype "passive"))
      (node (ref "C39") (pin "1") (pinfunction "1_1") (pintype "passive"))
      (node (ref "C40") (pin "1") (pinfunction "1_1") (pintype "passive"))
      (node (ref "C41") (pin "1") (pinfunction "1_1") (pintype "passive"))
      (node (ref "C42") (pin "1") (pinfunction "1_1") (pintype "passive"))
      (node (ref "C43") (pin "1") (pinfunction "1_1") (pintype "passive"))
      (node (ref "C44") (pin "1") (pinfunction "1_1") (pintype "passive"))
      (node (ref "C45") (pin "1") (pinfunction "1_1") (pintype "passive"))
      (node (ref "C46") (pin "1") (pinfunction "1_1") (pintype "passive"))
      (node (ref "C47") (pin "1") (pinfunction "1_1") (pintype "passive"))
      (node (ref "C48") (pin "1") (pinfunction "1_1") (pintype "passive"))
      (node (ref "C49") (pin "1") (pinfunction "1_1") (pintype "passive"))
      (node (ref "C50") (pin "1") (pinfunction "1_1") (pintype "passive"))
      (node (ref "C51") (pin "1") (pinfunction "1_1") (pintype "passive"))
      (node (ref "C52") (pin "1") (pinfunction "1_1") (pintype "passive"))
      (node (ref "C53") (pin "1") (pinfunction "1_1") (pintype "passive"))
      (node (ref "C54") (pin "1") (pinfunction "1_1") (pintype "passive"))
      (node (ref "C55") (pin "1") (pinfunction "1_1") (pintype "passive"))
      (node (ref "C56") (pin "1") (pinfunction "1_1") (pintype "passive"))
      (node (ref "C57") (pin "1") (pinfunction "1_1") (pintype "passive"))
      (node (ref "C58") (pin "1") (pinfunction "1_1") (pintype "passive"))
      (node (ref "C61") (pin "1") (pinfunction "1_1") (pintype "passive"))
      (node (ref "C62") (pin "1") (pinfunction "1_1") (pintype "passive"))
      (node (ref "C63") (pin "1") (pinfunction "1_1") (pintype "passive"))
      (node (ref "C64") (pin "2") (pinfunction "2_2") (pintype "passive"))
      (node (ref "C65") (pin "1") (pinfunction "1_1") (pintype "passive"))
      (node (ref "C66") (pin "1") (pinfunction "1_1") (pintype "passive"))
      (node (ref "D10") (pin "K") (pinfunction "K_K") (pintype "passive"))
      (node (ref "D11") (pin "K") (pinfunction "K_K") (pintype "passive"))
      (node (ref "D9") (pin "K") (pinfunction "K_K") (pintype "passive"))
      (node (ref "J3") (pin "2") (pinfunction "2_2") (pintype "passive"))
      (node (ref "J3") (pin "3") (pinfunction "3_3") (pintype "passive"))
      (node (ref "J3") (pin "4") (pinfunction "4_4") (pintype "passive"))
      (node (ref "J3") (pin "5") (pinfunction "5_5") (pintype "passive"))
      (node (ref "R35") (pin "1") (pinfunction "1_1") (pintype "passive"))
      (node (ref "RF1") (pin "1") (pinfunction "GND_1") (pintype "passive"))
      (node (ref "T1") (pin "2") (pinfunction "GND_2") (pintype "passive"))
      (node (ref "T1") (pin "5") (pinfunction "5_5") (pintype "passive"))
      (node (ref "U19") (pin "22") (pinfunction "FORCEON_22") (pintype "passive"))
      (node (ref "U19") (pin "23") (pinfunction "WAKEUP_23") (pintype "passive"))
      (node (ref "U19") (pin "32") (pinfunction "VSSIO_32") (pintype "passive"))
      (node (ref "U19") (pin "43") (pinfunction "VSSIO_43") (pintype "passive"))
      (node (ref "U19") (pin "46") (pinfunction "TESTMODE_46") (pintype "passive"))
      (node (ref "U19") (pin "49") (pinfunction "GND_49") (pintype "passive"))
    )
    (net (code "24") (name "Net-(C58-Pad2)") (class "Default")
      (node (ref "C58") (pin "2") (pinfunction "2_2") (pintype "passive"))
      (node (ref "U19") (pin "31") (pinfunction "VDDIO_31") (pintype "passive"))
    )
    (net (code "25") (name "Net-(C59-Pad1)") (class "Default")
      (node (ref "C59") (pin "1") (pinfunction "1_1") (pintype "passive"))
      (node (ref "T1") (pin "4") (pinfunction "4_4") (pintype "passive"))
    )
    (net (code "26") (name "Net-(C60-Pad1)") (class "Default")
      (node (ref "C60") (pin "1") (pinfunction "1_1") (pintype "passive"))
      (node (ref "T1") (pin "3") (pinfunction "3_3") (pintype "passive"))
    )
    (net (code "27") (name "Net-(C61-Pad2)") (class "Default")
      (node (ref "C61") (pin "2") (pinfunction "2_2") (pintype "passive"))
      (node (ref "U19") (pin "42") (pinfunction "VDDIO_42") (pintype "passive"))
    )
    (net (code "28") (name "Net-(C68-Pad2)") (class "Default")
      (node (ref "C68") (pin "2") (pinfunction "2_2") (pintype "passive"))
      (node (ref "R36") (pin "2") (pinfunction "2_2") (pintype "passive"))
    )
    (net (code "29") (name "Net-(C70-Pad2)") (class "Default")
      (node (ref "C70") (pin "2") (pinfunction "2_2") (pintype "passive"))
      (node (ref "R37") (pin "1") (pinfunction "1_1") (pintype "passive"))
    )
    (net (code "30") (name "Net-(D9-PadA)") (class "Default")
      (node (ref "D9") (pin "A") (pinfunction "A_A") (pintype "passive"))
      (node (ref "R32") (pin "1") (pinfunction "1_1") (pintype "passive"))
    )
    (net (code "31") (name "Net-(D10-PadA)") (class "Default")
      (node (ref "D10") (pin "A") (pinfunction "A_A") (pintype "passive"))
      (node (ref "R33") (pin "1") (pinfunction "1_1") (pintype "passive"))
    )
    (net (code "32") (name "Net-(D11-PadA)") (class "Default")
      (node (ref "D11") (pin "A") (pinfunction "A_A") (pintype "passive"))
      (node (ref "R34") (pin "1") (pinfunction "1_1") (pintype "passive"))
    )
    (net (code "33") (name "Net-(J3-Pad1)") (class "Default")
      (node (ref "J3") (pin "1") (pinfunction "1_1") (pintype "passive"))
      (node (ref "T1") (pin "1") (pinfunction "1_1") (pintype "passive"))
    )
    (net (code "34") (name "Net-(U19-CLKTUNE)") (class "Default")
      (node (ref "C69") (pin "1") (pinfunction "1_1") (pintype "passive"))
      (node (ref "R36") (pin "1") (pinfunction "1_1") (pintype "passive"))
      (node (ref "U19") (pin "8") (pinfunction "CLKTUNE_8") (pintype "passive"))
    )
    (net (code "35") (name "Net-(U19-GPIO5_{slash}_EXTTXE_{slash}_SPIPOL)") (class "Default")
      (node (ref "R39") (pin "2") (pinfunction "2_2") (pintype "passive"))
      (node (ref "U19") (pin "33") (pinfunction "GPIO5_/_EXTTXE_/_SPIPOL_33") (pintype "passive"))
    )
    (net (code "36") (name "Net-(U19-GPIO6_{slash}_EXTRXE_{slash}_SPIPHA)") (class "Default")
      (node (ref "R38") (pin "2") (pinfunction "2_2") (pintype "passive"))
      (node (ref "U19") (pin "30") (pinfunction "GPIO6_/_EXTRXE_/_SPIPHA_30") (pintype "passive"))
    )
    (net (code "37") (name "Net-(U19-VCOTUNE)") (class "Default")
      (node (ref "C67") (pin "2") (pinfunction "2_2") (pintype "passive"))
      (node (ref "R37") (pin "2") (pinfunction "2_2") (pintype "passive"))
      (node (ref "U19") (pin "12") (pinfunction "VCOTUNE_12") (pintype "passive"))
    )
    (net (code "38") (name "Net-(U19-VDDDIG)") (class "Default")
      (node (ref "C56") (pin "2") (pinfunction "2_2") (pintype "passive"))
      (node (ref "C63") (pin "2") (pinfunction "2_2") (pintype "passive"))
      (node (ref "U19") (pin "20") (pinfunction "VDDREG_20") (pintype "passive"))
      (node (ref "U19") (pin "44") (pinfunction "VDDDIG_44") (pintype "passive"))
    )
    (net (code "39") (name "Net-(U19-VDDIOA)") (class "Default")
      (node (ref "C64") (pin "1") (pinfunction "1_1") (pintype "passive"))
      (node (ref "U19") (pin "28") (pinfunction "VDDIOA_28") (pintype "passive"))
    )
    (net (code "40") (name "Net-(U19-VREF)") (class "Default")
      (node (ref "R35") (pin "2") (pinfunction "2_2") (pintype "passive"))
      (node (ref "U19") (pin "5") (pinfunction "VREF_5") (pintype "passive"))
    )
    (net (code "41") (name "Net-(U19-XTAL2)") (class "Default")
      (node (ref "C65") (pin "2") (pinfunction "2_2") (pintype "passive"))
      (node (ref "U19") (pin "4") (pinfunction "XTAL2_4") (pintype "passive"))
    )
    (net (code "42") (name "unconnected-(T1-NC-Pad6)") (class "Default")
      (node (ref "T1") (pin "6") (pinfunction "NC_6") (pintype "passive+no_connect"))
    )
    (net (code "43") (name "unconnected-(U19-GPIO0_{slash}_RXOKLED-Pad38)") (class "Default")
      (node (ref "U19") (pin "38") (pinfunction "GPIO0_/_RXOKLED_38") (pintype "passive+no_connect"))
    )
    (net (code "44") (name "unconnected-(U19-GPIO1_{slash}_SFDLED-Pad37)") (class "Default")
      (node (ref "U19") (pin "37") (pinfunction "GPIO1_/_SFDLED_37") (pintype "passive+no_connect"))
    )
    (net (code "45") (name "unconnected-(U19-GPIO4_{slash}_EXTPA-Pad34)") (class "Default")
      (node (ref "U19") (pin "34") (pinfunction "GPIO4_/_EXTPA_34") (pintype "passive+no_connect"))
    )
    (net (code "46") (name "unconnected-(U19-NC-Pad1)") (class "Default")
      (node (ref "U19") (pin "1") (pinfunction "NC_1") (pintype "passive+no_connect"))
    )
    (net (code "47") (name "unconnected-(U19-NC-Pad2)") (class "Default")
      (node (ref "U19") (pin "2") (pinfunction "NC_2") (pintype "passive+no_connect"))
    )
    (net (code "48") (name "unconnected-(U19-NC-Pad13)") (class "Default")
      (node (ref "U19") (pin "13") (pinfunction "NC_13") (pintype "passive+no_connect"))
    )
    (net (code "49") (name "unconnected-(U19-NC-Pad14)") (class "Default")
      (node (ref "U19") (pin "14") (pinfunction "NC_14") (pintype "passive+no_connect"))
    )
  )
)
